# Can_Bus_Tranciever.net
KiCad netlist of a schematic drawn in Altium Designer
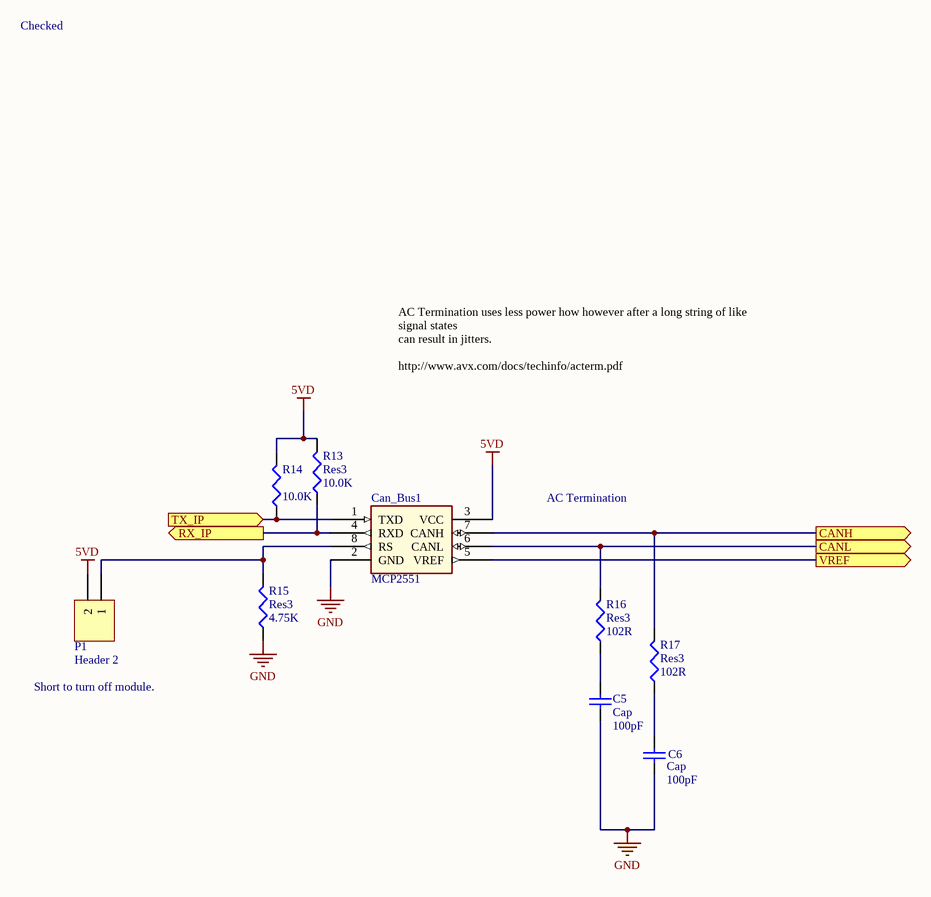
[diagram p0: Can_Bus_Tranciever.SchDoc]

(export (version "E")
  (design (tool "Eeschema 10.0.6"))
  (components
    (comp (ref "C5")
      (value "Cap")
      (footprint "CAPC2012X09M")
      (description "CAP CER 100pF 500v COG 0805")
      (fields (field (name "ALTIUM_VALUE") "100pF") (field (name "MPN") "C0805C101JCGACTU"))
      (libsource (lib "esd_library") (part "CAP-COG-100pF-500V-±5%"))
    )
    (comp (ref "C6")
      (value "Cap")
      (footprint "CAPC2012X09M")
      (description "CAP CER 100pF 500v COG 0805")
      (fields (field (name "ALTIUM_VALUE") "100pF") (field (name "MPN") "C0805C101JCGACTU"))
      (libsource (lib "esd_library") (part "CAP-COG-100pF-500V-±5%"))
    )
    (comp (ref "Can_Bus1")
      (value "MCP2551")
      (footprint "SOIC127P600X175-8M")
      (description "IC TRANSCEIVER CAN HI-SPD 8-SOIC")
      (fields (field (name "MPN") "MCP2551T-E/SN"))
      (libsource (lib "esd_library") (part "MCP2551"))
    )
    (comp (ref "P1")
      (value "Header 2")
      (footprint "HDR1X2")
      (description "Header, 2-Pin Male")
      (fields (field (name "MPN") "PEC02SFAN"))
      (libsource (lib "esd_library (1)") (part "Header 2"))
    )
    (comp (ref "R13")
      (value "Res3")
      (footprint "RESC2112X05M")
      (description "RES SMD 10.0K OHM 1% 1/8W 0805")
      (fields (field (name "ALTIUM_VALUE") "10.0K") (field (name "MPN") "CRCW080510K0FKEA"))
      (libsource (lib "esd_library") (part "Resistor_10.0K"))
    )
    (comp (ref "R14")
      (value "10.0K")
      (footprint "RESC2112X05M")
      (description "RES SMD 10.0K OHM 1% 1/8W 0805")
      (fields (field (name "MPN") "CRCW080510K0FKEA") (field (name "Comment") "Res3"))
      (libsource (lib "esd_library") (part "Resistor_10.0K"))
    )
    (comp (ref "R15")
      (value "Res3")
      (footprint "RESC2112X05M")
      (description "RES SMD 4.75K OHM 1% 1/8W 0805")
      (fields (field (name "ALTIUM_VALUE") "4.75K") (field (name "MPN") "CRCW08054K75FKEA"))
      (libsource (lib "esd_library") (part "Resistor_4.75K"))
    )
    (comp (ref "R16")
      (value "Res3")
      (footprint "RESC2112X05M")
      (description "RES SMD 102R OHM 1% 1/8W 0805")
      (fields (field (name "ALTIUM_VALUE") "102R") (field (name "MPN") "CRCW0805102RFKEA"))
      (libsource (lib "esd_library") (part "Resistor_102R"))
    )
    (comp (ref "R17")
      (value "Res3")
      (footprint "RESC2112X05M")
      (description "RES SMD 102R OHM 1% 1/8W 0805")
      (fields (field (name "ALTIUM_VALUE") "102R") (field (name "MPN") "CRCW0805102RFKEA"))
      (libsource (lib "esd_library") (part "Resistor_102R"))
    )
  )
  (nets
    (net (code "1") (name "/CANH") (class "Default")
      (node (ref "Can_Bus1") (pin "7") (pinfunction "CANH_7") (pintype "bidirectional"))
      (node (ref "R17") (pin "2") (pinfunction "2_2") (pintype "passive"))
    )
    (net (code "2") (name "/CANL") (class "Default")
      (node (ref "Can_Bus1") (pin "6") (pinfunction "CANL_6") (pintype "bidirectional"))
      (node (ref "R16") (pin "2") (pinfunction "2_2") (pintype "passive"))
    )
    (net (code "3") (name "/RX_IP") (class "Default")
      (node (ref "Can_Bus1") (pin "4") (pinfunction "RXD_4") (pintype "output"))
      (node (ref "R13") (pin "1") (pinfunction "1_1") (pintype "passive"))
    )
    (net (code "4") (name "/TX_IP") (class "Default")
      (node (ref "Can_Bus1") (pin "1") (pinfunction "TXD_1") (pintype "input"))
      (node (ref "R14") (pin "1") (pinfunction "1_1") (pintype "passive"))
    )
    (net (code "5") (name "/VREF") (class "Default")
      (node (ref "Can_Bus1") (pin "5") (pinfunction "VREF_5") (pintype "output"))
    )
    (net (code "6") (name "5VD") (class "Default")
      (node (ref "Can_Bus1") (pin "3") (pinfunction "VCC_3") (pintype "power_in"))
      (node (ref "P1") (pin "2") (pinfunction "2_2") (pintype "passive"))
      (node (ref "R13") (pin "2") (pinfunction "2_2") (pintype "passive"))
      (node (ref "R14") (pin "2") (pinfunction "2_2") (pintype "passive"))
    )
    (net (code "7") (name "GND") (class "Default")
      (node (ref "C5") (pin "1") (pinfunction "1_1") (pintype "passive"))
      (node (ref "C6") (pin "1") (pinfunction "1_1") (pintype "passive"))
      (node (ref "Can_Bus1") (pin "2") (pinfunction "GND_2") (pintype "power_in"))
      (node (ref "R15") (pin "1") (pinfunction "1_1") (pintype "passive"))
    )
    (net (code "8") (name "Net-(C5-Pad2)") (class "Default")
      (node (ref "C5") (pin "2") (pinfunction "2_2") (pintype "passive"))
      (node (ref "R16") (pin "1") (pinfunction "1_1") (pintype "passive"))
    )
    (net (code "9") (name "Net-(C6-Pad2)") (class "Default")
      (node (ref "C6") (pin "2") (pinfunction "2_2") (pintype "passive"))
      (node (ref "R17") (pin "1") (pinfunction "1_1") (pintype "passive"))
    )
    (net (code "10") (name "Net-(Can_Bus1-RS)") (class "Default")
      (node (ref "Can_Bus1") (pin "8") (pinfunction "RS_8") (pintype "output"))
      (node (ref "P1") (pin "1") (pinfunction "1_1") (pintype "passive"))
      (node (ref "R15") (pin "2") (pinfunction "2_2") (pintype "passive"))
    )
  )
)
